# Sheet1.net
KiCad netlist of a schematic drawn in Altium Designer
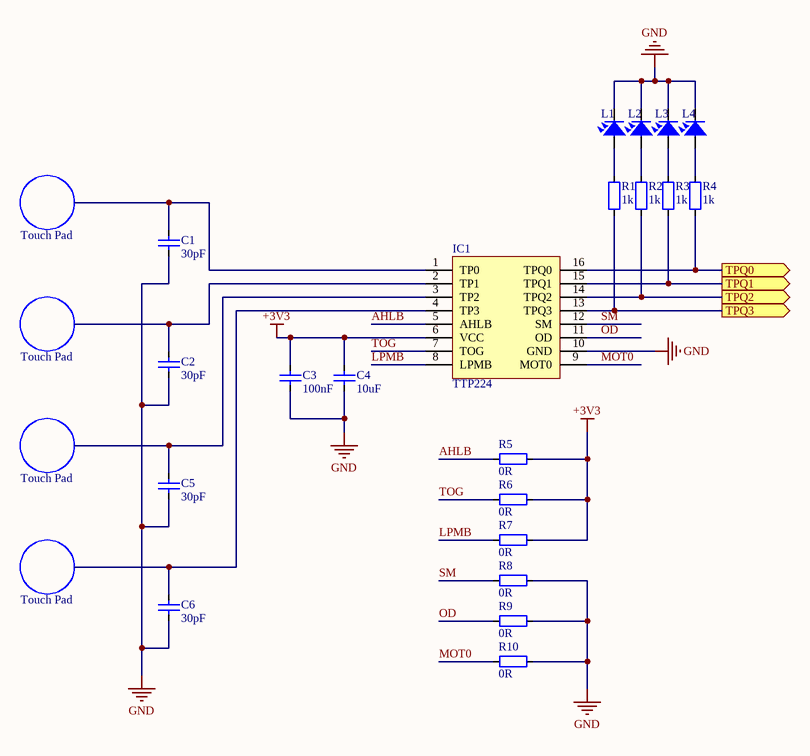
[diagram p0: Sheet1.SchDoc]

(export (version "E")
  (design (tool "Eeschema 10.0.6"))
  (components
    (comp (ref "C1")
      (value "30pF")
      (footprint "CAP_0805")
      (description "Capacitor")
      (fields (field (name "PUBLISHER") "Altium Limited"))
      (libsource (lib "My Library") (part "CapSMD"))
    )
    (comp (ref "C2")
      (value "30pF")
      (footprint "CAP_0805")
      (description "Capacitor")
      (fields (field (name "PUBLISHER") "Altium Limited"))
      (libsource (lib "My Library") (part "CapSMD"))
    )
    (comp (ref "C3")
      (value "100nF")
      (footprint "CAP_0805")
      (description "Capacitor")
      (fields (field (name "PUBLISHER") "Altium Limited"))
      (libsource (lib "My Library") (part "CapSMD"))
    )
    (comp (ref "C4")
      (value "10uF")
      (footprint "CAP_0805")
      (description "Capacitor")
      (fields (field (name "PUBLISHER") "Altium Limited"))
      (libsource (lib "My Library") (part "CapSMD"))
    )
    (comp (ref "C5")
      (value "30pF")
      (footprint "CAP_0805")
      (description "Capacitor")
      (fields (field (name "PUBLISHER") "Altium Limited"))
      (libsource (lib "My Library") (part "CapSMD"))
    )
    (comp (ref "C6")
      (value "30pF")
      (footprint "CAP_0805")
      (description "Capacitor")
      (fields (field (name "PUBLISHER") "Altium Limited"))
      (libsource (lib "My Library") (part "CapSMD"))
    )
    (comp (ref "IC1") (value "TTP224") (libsource (lib "My Library") (part "TTP224")))
    (comp (ref "L1")
      (value "LED")
      (footprint "LED-0805-Red")
      (description "LED Single colour Green and Red")
      (libsource (lib "My Library") (part "LED"))
    )
    (comp (ref "L2")
      (value "LED")
      (footprint "LED-0805-Red")
      (description "LED Single colour Green and Red")
      (libsource (lib "My Library") (part "LED"))
    )
    (comp (ref "L3")
      (value "LED")
      (footprint "LED-0805-Red")
      (description "LED Single colour Green and Red")
      (libsource (lib "My Library") (part "LED"))
    )
    (comp (ref "L4")
      (value "LED")
      (footprint "LED-0805-Red")
      (description "LED Single colour Green and Red")
      (libsource (lib "My Library") (part "LED"))
    )
    (comp (ref "R1")
      (value "1k")
      (footprint "RES-SMD-0805")
      (description "Resistor")
      (fields
        (field (name "MANUFACTURER") "Generic Components")
        (field (name "PUBLISHER") "Altium Hobart Technology Centre")
      )
      (libsource (lib "My Library") (part "Resistor - SMD"))
    )
    (comp (ref "R2")
      (value "1k")
      (footprint "RES-SMD-0805")
      (description "Resistor")
      (fields
        (field (name "MANUFACTURER") "Generic Components")
        (field (name "PUBLISHER") "Altium Hobart Technology Centre")
      )
      (libsource (lib "My Library") (part "Resistor - SMD"))
    )
    (comp (ref "R3")
      (value "1k")
      (footprint "RES-SMD-0805")
      (description "Resistor")
      (fields
        (field (name "MANUFACTURER") "Generic Components")
        (field (name "PUBLISHER") "Altium Hobart Technology Centre")
      )
      (libsource (lib "My Library") (part "Resistor - SMD"))
    )
    (comp (ref "R4")
      (value "1k")
      (footprint "RES-SMD-0805")
      (description "Resistor")
      (fields
        (field (name "MANUFACTURER") "Generic Components")
        (field (name "PUBLISHER") "Altium Hobart Technology Centre")
      )
      (libsource (lib "My Library") (part "Resistor - SMD"))
    )
    (comp (ref "R5")
      (value "0R")
      (footprint "RES-SMD-0805")
      (description "Resistor")
      (fields
        (field (name "MANUFACTURER") "Generic Components")
        (field (name "PUBLISHER") "Altium Hobart Technology Centre")
      )
      (libsource (lib "My Library") (part "Resistor - SMD"))
    )
    (comp (ref "R6")
      (value "0R")
      (footprint "RES-SMD-0805")
      (description "Resistor")
      (fields
        (field (name "MANUFACTURER") "Generic Components")
        (field (name "PUBLISHER") "Altium Hobart Technology Centre")
      )
      (libsource (lib "My Library") (part "Resistor - SMD"))
    )
    (comp (ref "R7")
      (value "0R")
      (footprint "RES-SMD-0805")
      (description "Resistor")
      (fields
        (field (name "MANUFACTURER") "Generic Components")
        (field (name "PUBLISHER") "Altium Hobart Technology Centre")
      )
      (libsource (lib "My Library") (part "Resistor - SMD"))
    )
    (comp (ref "R8")
      (value "0R")
      (footprint "RES-SMD-0805")
      (description "Resistor")
      (fields
        (field (name "MANUFACTURER") "Generic Components")
        (field (name "PUBLISHER") "Altium Hobart Technology Centre")
      )
      (libsource (lib "My Library") (part "Resistor - SMD"))
    )
    (comp (ref "R9")
      (value "0R")
      (footprint "RES-SMD-0805")
      (description "Resistor")
      (fields
        (field (name "MANUFACTURER") "Generic Components")
        (field (name "PUBLISHER") "Altium Hobart Technology Centre")
      )
      (libsource (lib "My Library") (part "Resistor - SMD"))
    )
    (comp (ref "R10")
      (value "0R")
      (footprint "RES-SMD-0805")
      (description "Resistor")
      (fields
        (field (name "MANUFACTURER") "Generic Components")
        (field (name "PUBLISHER") "Altium Hobart Technology Centre")
      )
      (libsource (lib "My Library") (part "Resistor - SMD"))
    )
  )
  (nets
    (net (code "1") (name "+3V3") (class "Default")
      (node (ref "C3") (pin "2") (pinfunction "2_2") (pintype "passive"))
      (node (ref "C4") (pin "2") (pinfunction "2_2") (pintype "passive"))
      (node (ref "IC1") (pin "6") (pinfunction "VCC_6") (pintype "passive"))
      (node (ref "R5") (pin "2") (pinfunction "2_2") (pintype "passive"))
      (node (ref "R6") (pin "2") (pinfunction "2_2") (pintype "passive"))
      (node (ref "R7") (pin "2") (pinfunction "2_2") (pintype "passive"))
    )
    (net (code "2") (name "/AHLB") (class "Default")
      (node (ref "IC1") (pin "5") (pinfunction "AHLB_5") (pintype "passive"))
      (node (ref "R5") (pin "1") (pinfunction "1_1") (pintype "passive"))
    )
    (net (code "3") (name "/LPMB") (class "Default")
      (node (ref "IC1") (pin "8") (pinfunction "LPMB_8") (pintype "passive"))
      (node (ref "R7") (pin "1") (pinfunction "1_1") (pintype "passive"))
    )
    (net (code "4") (name "/MOT0") (class "Default")
      (node (ref "IC1") (pin "9") (pinfunction "MOT0_9") (pintype "passive"))
      (node (ref "R10") (pin "1") (pinfunction "1_1") (pintype "passive"))
    )
    (net (code "5") (name "/OD") (class "Default")
      (node (ref "IC1") (pin "11") (pinfunction "OD_11") (pintype "passive"))
      (node (ref "R9") (pin "1") (pinfunction "1_1") (pintype "passive"))
    )
    (net (code "6") (name "/SM") (class "Default")
      (node (ref "IC1") (pin "12") (pinfunction "SM_12") (pintype "passive"))
      (node (ref "R8") (pin "1") (pinfunction "1_1") (pintype "passive"))
    )
    (net (code "7") (name "/TOG") (class "Default")
      (node (ref "IC1") (pin "7") (pinfunction "TOG_7") (pintype "passive"))
      (node (ref "R6") (pin "1") (pinfunction "1_1") (pintype "passive"))
    )
    (net (code "8") (name "/TPQ0") (class "Default")
      (node (ref "IC1") (pin "16") (pinfunction "TPQ0_16") (pintype "passive"))
      (node (ref "R4") (pin "1") (pinfunction "1_1") (pintype "passive"))
    )
    (net (code "9") (name "/TPQ1") (class "Default")
      (node (ref "IC1") (pin "15") (pinfunction "TPQ1_15") (pintype "passive"))
      (node (ref "R3") (pin "1") (pinfunction "1_1") (pintype "passive"))
    )
    (net (code "10") (name "/TPQ2") (class "Default")
      (node (ref "IC1") (pin "14") (pinfunction "TPQ2_14") (pintype "passive"))
      (node (ref "R2") (pin "1") (pinfunction "1_1") (pintype "passive"))
    )
    (net (code "11") (name "/TPQ3") (class "Default")
      (node (ref "IC1") (pin "13") (pinfunction "TPQ3_13") (pintype "passive"))
      (node (ref "R1") (pin "1") (pinfunction "1_1") (pintype "passive"))
    )
    (net (code "12") (name "GND") (class "Default")
      (node (ref "C1") (pin "1") (pinfunction "1_1") (pintype "passive"))
      (node (ref "C2") (pin "1") (pinfunction "1_1") (pintype "passive"))
      (node (ref "C3") (pin "1") (pinfunction "1_1") (pintype "passive"))
      (node (ref "C4") (pin "1") (pinfunction "1_1") (pintype "passive"))
      (node (ref "C5") (pin "1") (pinfunction "1_1") (pintype "passive"))
      (node (ref "C6") (pin "1") (pinfunction "1_1") (pintype "passive"))
      (node (ref "IC1") (pin "10") (pinfunction "GND_10") (pintype "passive"))
      (node (ref "L1") (pin "2") (pinfunction "2_2") (pintype "passive"))
      (node (ref "L2") (pin "2") (pinfunction "2_2") (pintype "passive"))
      (node (ref "L3") (pin "2") (pinfunction "2_2") (pintype "passive"))
      (node (ref "L4") (pin "2") (pinfunction "2_2") (pintype "passive"))
      (node (ref "R10") (pin "2") (pinfunction "2_2") (pintype "passive"))
      (node (ref "R8") (pin "2") (pinfunction "2_2") (pintype "passive"))
      (node (ref "R9") (pin "2") (pinfunction "2_2") (pintype "passive"))
    )
    (net (code "13") (name "Net-(IC1-TP0)") (class "Default")
      (node (ref "C1") (pin "2") (pinfunction "2_2") (pintype "passive"))
      (node (ref "IC1") (pin "1") (pinfunction "TP0_1") (pintype "passive"))
    )
    (net (code "14") (name "Net-(IC1-TP1)") (class "Default")
      (node (ref "C2") (pin "2") (pinfunction "2_2") (pintype "passive"))
      (node (ref "IC1") (pin "2") (pinfunction "TP1_2") (pintype "passive"))
    )
    (net (code "15") (name "Net-(IC1-TP2)") (class "Default")
      (node (ref "C5") (pin "2") (pinfunction "2_2") (pintype "passive"))
      (node (ref "IC1") (pin "3") (pinfunction "TP2_3") (pintype "passive"))
    )
    (net (code "16") (name "Net-(IC1-TP3)") (class "Default")
      (node (ref "C6") (pin "2") (pinfunction "2_2") (pintype "passive"))
      (node (ref "IC1") (pin "4") (pinfunction "TP3_4") (pintype "passive"))
    )
    (net (code "17") (name "Net-(L1-Pad1)") (class "Default")
      (node (ref "L1") (pin "1") (pinfunction "1_1") (pintype "passive"))
      (node (ref "R1") (pin "2") (pinfunction "2_2") (pintype "passive"))
    )
    (net (code "18") (name "Net-(L2-Pad1)") (class "Default")
      (node (ref "L2") (pin "1") (pinfunction "1_1") (pintype "passive"))
      (node (ref "R2") (pin "2") (pinfunction "2_2") (pintype "passive"))
    )
    (net (code "19") (name "Net-(L3-Pad1)") (class "Default")
      (node (ref "L3") (pin "1") (pinfunction "1_1") (pintype "passive"))
      (node (ref "R3") (pin "2") (pinfunction "2_2") (pintype "passive"))
    )
    (net (code "20") (name "Net-(L4-Pad1)") (class "Default")
      (node (ref "L4") (pin "1") (pinfunction "1_1") (pintype "passive"))
      (node (ref "R4") (pin "2") (pinfunction "2_2") (pintype "passive"))
    )
  )
)
